# Dispenser.net
KiCad netlist of a schematic drawn in EAGLE
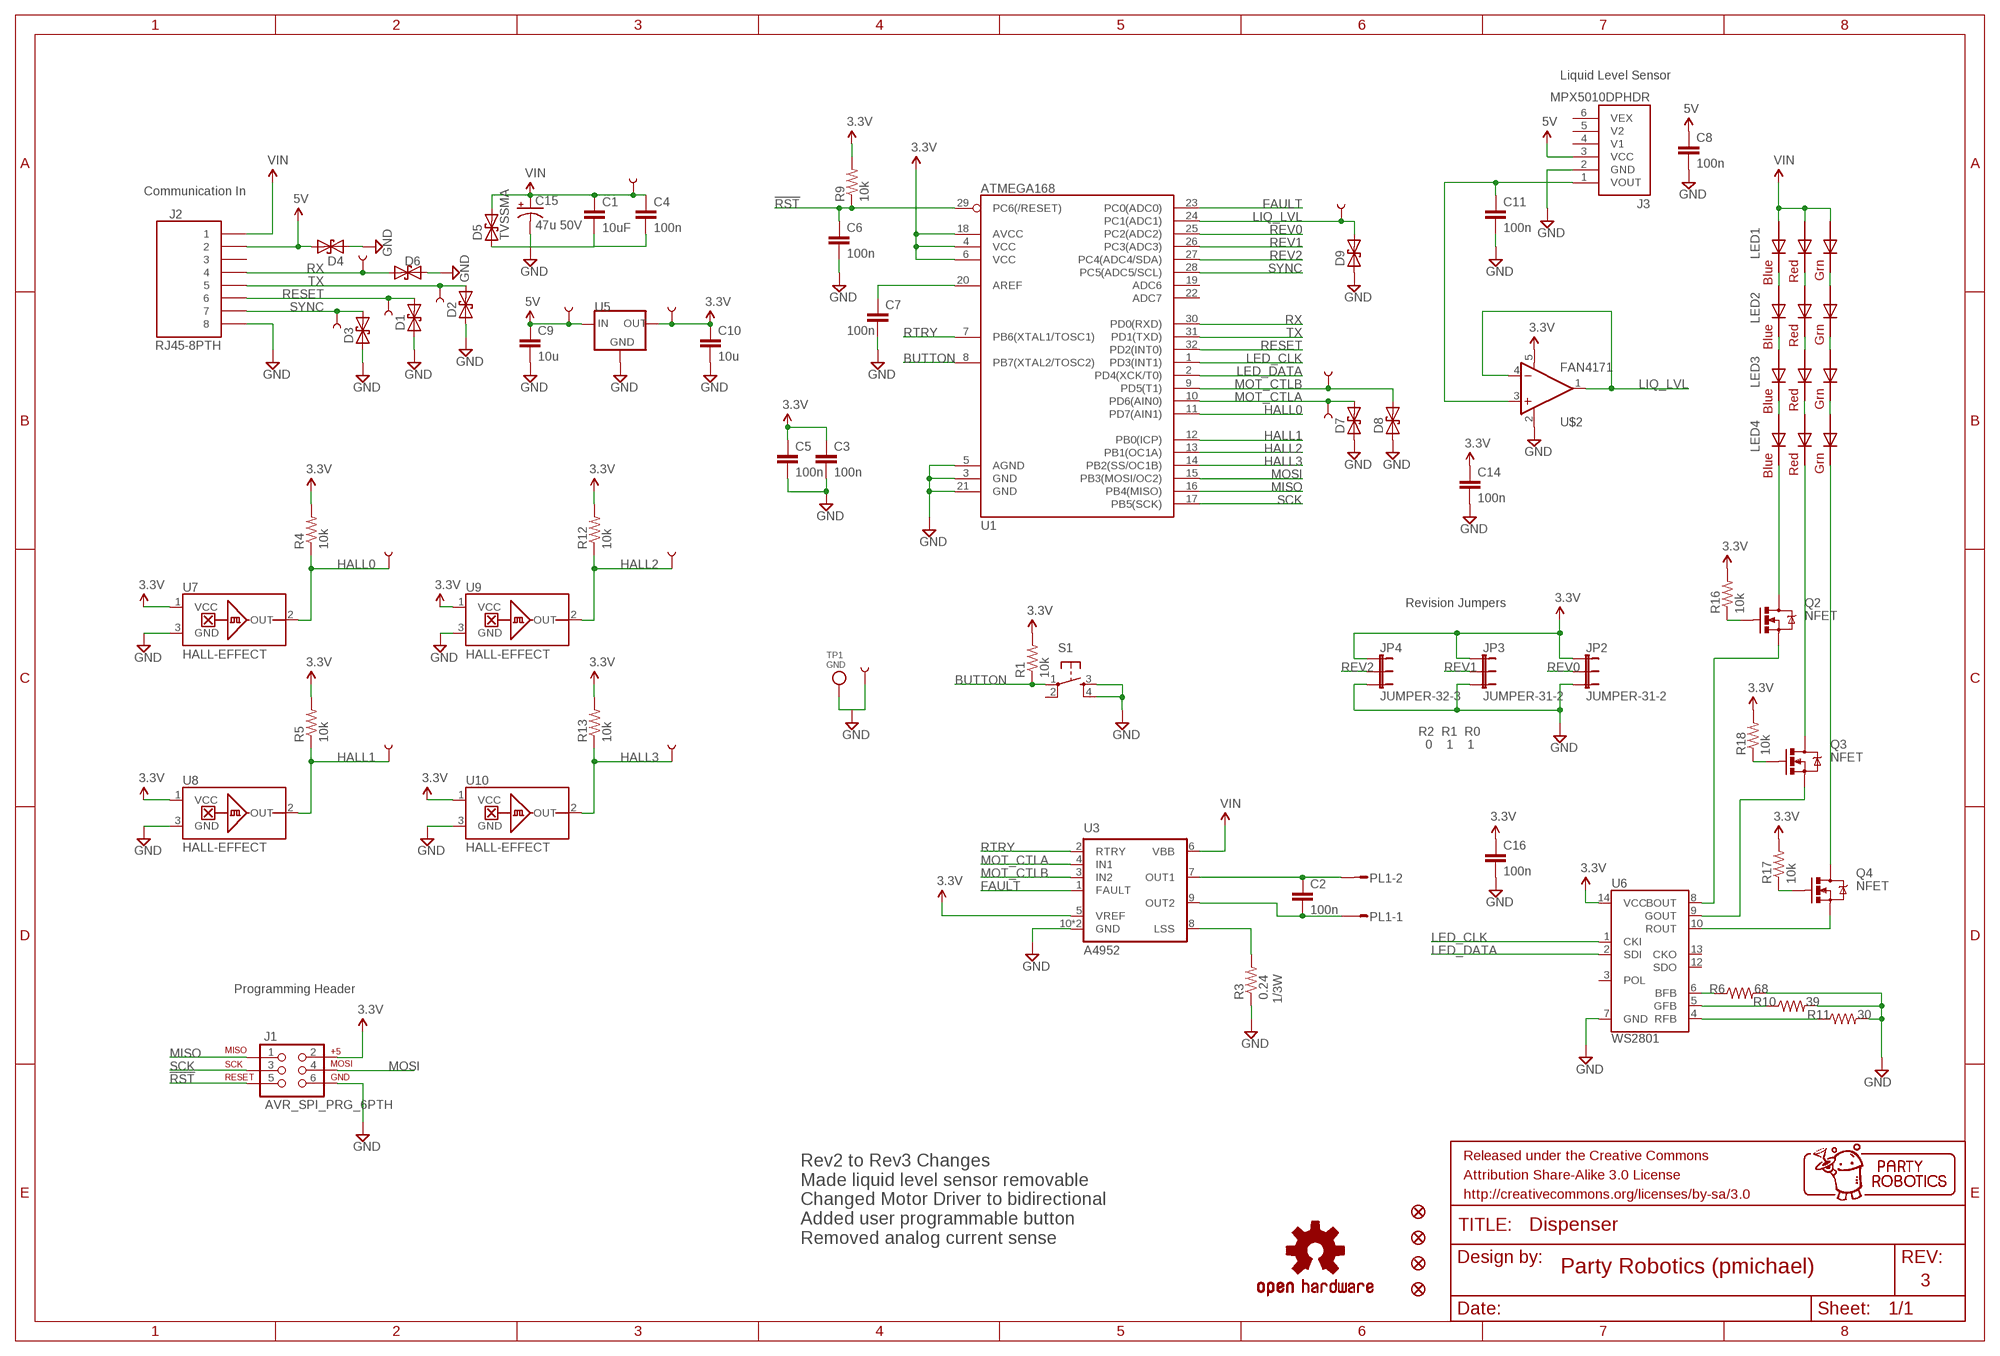
[diagram p0: schematic, sheet 1]

(export (version "E")
  (design (tool "Eeschema 10.0.6"))
  (components
    (comp (ref "C1")
      (value "10uF")
      (footprint "eagle-import:1206")
      (libsource (lib "eagle-import") (part "2.2UF-CERCAP-10009"))
    )
    (comp (ref "C2")
      (value "100n")
      (footprint "eagle-import:0603-CAP")
      (libsource (lib "eagle-import") (part "CAP0603-CAP"))
    )
    (comp (ref "C3")
      (value "100n")
      (footprint "eagle-import:0603-CAP")
      (libsource (lib "eagle-import") (part "CAP0603-CAP"))
    )
    (comp (ref "C4")
      (value "100n")
      (footprint "eagle-import:0603-CAP")
      (libsource (lib "eagle-import") (part "CAP0603-CAP"))
    )
    (comp (ref "C5")
      (value "100n")
      (footprint "eagle-import:0603-CAP")
      (libsource (lib "eagle-import") (part "CAP0603-CAP"))
    )
    (comp (ref "C6")
      (value "100n")
      (footprint "eagle-import:0603-CAP")
      (libsource (lib "eagle-import") (part "CAP0603-CAP"))
    )
    (comp (ref "C7")
      (value "100n")
      (footprint "eagle-import:0603-CAP")
      (libsource (lib "eagle-import") (part "CAP0603-CAP"))
    )
    (comp (ref "C8")
      (value "100n")
      (footprint "eagle-import:0603-CAP")
      (libsource (lib "eagle-import") (part "CAP0603-CAP"))
    )
    (comp (ref "C9")
      (value "10u")
      (footprint "eagle-import:0603-CAP")
      (libsource (lib "eagle-import") (part "SparkFun-Passives_CAP0603-CAP"))
    )
    (comp (ref "C10")
      (value "10u")
      (footprint "eagle-import:0603-CAP")
      (libsource (lib "eagle-import") (part "SparkFun-Passives_CAP0603-CAP"))
    )
    (comp (ref "C11")
      (value "100n")
      (footprint "eagle-import:0603-CAP")
      (libsource (lib "eagle-import") (part "CAP0603-CAP"))
    )
    (comp (ref "C14")
      (value "100n")
      (footprint "eagle-import:0603-CAP")
      (libsource (lib "eagle-import") (part "CAP0603-CAP"))
    )
    (comp (ref "C15")
      (value "47u 50V")
      (footprint "eagle-import:PANASONIC_D")
      (libsource (lib "eagle-import") (part "CAP_POLD"))
    )
    (comp (ref "C16")
      (value "100n")
      (footprint "eagle-import:0603-CAP")
      (libsource (lib "eagle-import") (part "CAP0603-CAP"))
    )
    (comp (ref "D1")
      (value "TVSSOD-923")
      (footprint "eagle-import:SOD-923")
      (libsource (lib "eagle-import") (part "TVSSOD-923"))
    )
    (comp (ref "D2")
      (value "TVSSOD-923")
      (footprint "eagle-import:SOD-923")
      (libsource (lib "eagle-import") (part "TVSSOD-923"))
    )
    (comp (ref "D3")
      (value "TVSSOD-923")
      (footprint "eagle-import:SOD-923")
      (libsource (lib "eagle-import") (part "TVSSOD-923"))
    )
    (comp (ref "D4")
      (value "TVSSOD-923")
      (footprint "eagle-import:SOD-923")
      (libsource (lib "eagle-import") (part "TVSSOD-923"))
    )
    (comp (ref "D5")
      (value "TVSSMA")
      (footprint "eagle-import:SMA-DIODE")
      (fields (field (name "MFG") "Bourns"))
      (libsource (lib "eagle-import") (part "TVSSMA"))
    )
    (comp (ref "D6")
      (value "TVSSOD-923")
      (footprint "eagle-import:SOD-923")
      (libsource (lib "eagle-import") (part "TVSSOD-923"))
    )
    (comp (ref "D7")
      (value "TVSSOD-923")
      (footprint "eagle-import:SOD-923")
      (libsource (lib "eagle-import") (part "TVSSOD-923"))
    )
    (comp (ref "D8")
      (value "TVSSOD-923")
      (footprint "eagle-import:SOD-923")
      (libsource (lib "eagle-import") (part "TVSSOD-923"))
    )
    (comp (ref "D9")
      (value "TVSSOD-923")
      (footprint "eagle-import:SOD-923")
      (libsource (lib "eagle-import") (part "TVSSOD-923"))
    )
    (comp (ref "FRAME3")
      (value "FRAME-LETTER")
      (footprint "eagle-import:CREATIVE_COMMONS")
      (libsource (lib "eagle-import") (part "FRAME-LETTER"))
    )
    (comp (ref "J1")
      (value "AVR_SPI_PRG_6PTH")
      (footprint "eagle-import:2X3")
      (libsource (lib "eagle-import") (part "AVR_SPI_PRG_6PTH"))
    )
    (comp (ref "J2")
      (value "RJ45-8PTH")
      (footprint "eagle-import:RJ45-8")
      (fields (field (name "MFG") "EDAC Inc"))
      (libsource (lib "eagle-import") (part "RJ45-8PTH"))
    )
    (comp (ref "J3")
      (value "MPX5010DPHDR")
      (footprint "eagle-import:MPX5010_HDR")
      (libsource (lib "eagle-import") (part "MPX5010DPHDR"))
    )
    (comp (ref "JP2")
      (value "JUMPER-31-2")
      (footprint "eagle-import:SJ_3_PASTE1&2")
      (libsource (lib "eagle-import") (part "JUMPER-31-2"))
    )
    (comp (ref "JP3")
      (value "JUMPER-31-2")
      (footprint "eagle-import:SJ_3_PASTE1&2")
      (libsource (lib "eagle-import") (part "JUMPER-31-2"))
    )
    (comp (ref "JP4")
      (value "JUMPER-32-3")
      (footprint "eagle-import:SJ_3_PASTE2&3")
      (libsource (lib "eagle-import") (part "JUMPER-32-3"))
    )
    (comp (ref "JP5")
      (value "FIDUCIAL1X2")
      (footprint "eagle-import:FIDUCIAL-1X2")
      (libsource (lib "eagle-import") (part "FIDUCIAL1X2"))
    )
    (comp (ref "JP6")
      (value "FIDUCIAL1X2")
      (footprint "eagle-import:FIDUCIAL-1X2")
      (libsource (lib "eagle-import") (part "FIDUCIAL1X2"))
    )
    (comp (ref "JP7")
      (value "FIDUCIAL1X2")
      (footprint "eagle-import:FIDUCIAL-1X2")
      (libsource (lib "eagle-import") (part "FIDUCIAL1X2"))
    )
    (comp (ref "JP8")
      (value "FIDUCIAL1X2")
      (footprint "eagle-import:FIDUCIAL-1X2")
      (libsource (lib "eagle-import") (part "FIDUCIAL1X2"))
    )
    (comp (ref "LED1")
      (value "RGBLED5050")
      (footprint "eagle-import:RGBLED5050")
      (libsource (lib "eagle-import") (part "RGBLED5050"))
    )
    (comp (ref "LED2")
      (value "RGBLED5050")
      (footprint "eagle-import:RGBLED5050")
      (libsource (lib "eagle-import") (part "RGBLED5050"))
    )
    (comp (ref "LED3")
      (value "RGBLED5050")
      (footprint "eagle-import:RGBLED5050")
      (libsource (lib "eagle-import") (part "RGBLED5050"))
    )
    (comp (ref "LED4")
      (value "RGBLED5050")
      (footprint "eagle-import:RGBLED5050")
      (libsource (lib "eagle-import") (part "RGBLED5050"))
    )
    (comp (ref "PL1")
      (value "DF3-02P")
      (footprint "eagle-import:DF3P-02")
      (libsource (lib "eagle-import") (part "DF3-02P"))
    )
    (comp (ref "Q2")
      (value "NFET")
      (footprint "eagle-import:SOT23-3")
      (libsource (lib "eagle-import") (part "MOSFET-NCHANNELSMD"))
    )
    (comp (ref "Q3")
      (value "NFET")
      (footprint "eagle-import:SOT23-3")
      (libsource (lib "eagle-import") (part "MOSFET-NCHANNELSMD"))
    )
    (comp (ref "Q4")
      (value "NFET")
      (footprint "eagle-import:SOT23-3")
      (libsource (lib "eagle-import") (part "MOSFET-NCHANNELSMD"))
    )
    (comp (ref "R1")
      (value "10k")
      (footprint "eagle-import:0603-RES")
      (libsource (lib "eagle-import") (part "RESISTOR0603-RES"))
    )
    (comp (ref "R3")
      (value "0.24")
      (footprint "eagle-import:0805")
      (libsource (lib "eagle-import") (part "RESISTOR0805-RES"))
    )
    (comp (ref "R4")
      (value "10k")
      (footprint "eagle-import:0603-RES")
      (libsource (lib "eagle-import") (part "RESISTOR0603-RES"))
    )
    (comp (ref "R5")
      (value "10k")
      (footprint "eagle-import:0603-RES")
      (libsource (lib "eagle-import") (part "RESISTOR0603-RES"))
    )
    (comp (ref "R6")
      (value "68")
      (footprint "eagle-import:0603-RES")
      (libsource (lib "eagle-import") (part "RESISTOR0603-RES"))
    )
    (comp (ref "R9")
      (value "10k")
      (footprint "eagle-import:0603-RES")
      (libsource (lib "eagle-import") (part "RESISTOR0603-RES"))
    )
    (comp (ref "R10")
      (value "39")
      (footprint "eagle-import:0603-RES")
      (libsource (lib "eagle-import") (part "RESISTOR0603-RES"))
    )
    (comp (ref "R11")
      (value "30")
      (footprint "eagle-import:0603-RES")
      (libsource (lib "eagle-import") (part "RESISTOR0603-RES"))
    )
    (comp (ref "R12")
      (value "10k")
      (footprint "eagle-import:0603-RES")
      (libsource (lib "eagle-import") (part "RESISTOR0603-RES"))
    )
    (comp (ref "R13")
      (value "10k")
      (footprint "eagle-import:0603-RES")
      (libsource (lib "eagle-import") (part "RESISTOR0603-RES"))
    )
    (comp (ref "R16")
      (value "10k")
      (footprint "eagle-import:0603-RES")
      (libsource (lib "eagle-import") (part "RESISTOR0603-RES"))
    )
    (comp (ref "R17")
      (value "10k")
      (footprint "eagle-import:0603-RES")
      (libsource (lib "eagle-import") (part "RESISTOR0603-RES"))
    )
    (comp (ref "R18")
      (value "10k")
      (footprint "eagle-import:0603-RES")
      (libsource (lib "eagle-import") (part "RESISTOR0603-RES"))
    )
    (comp (ref "S1")
      (value "TAC_SWITCHSMD")
      (footprint "eagle-import:TACTILE_SWITCH_SMD")
      (libsource (lib "eagle-import") (part "TAC_SWITCHSMD"))
    )
    (comp (ref "TP1")
      (value "GND")
      (footprint "eagle-import:TESTPOINT_SMT")
      (libsource (lib "eagle-import") (part "TESTPOINT"))
    )
    (comp (ref "TP2")
      (value "TEST-POINT0.08")
      (footprint "eagle-import:PAD_0.08")
      (libsource (lib "eagle-import") (part "TEST-POINT0.08"))
    )
    (comp (ref "TP3")
      (value "TEST-POINT0.08")
      (footprint "eagle-import:PAD_0.08")
      (libsource (lib "eagle-import") (part "TEST-POINT0.08"))
    )
    (comp (ref "TP4")
      (value "TEST-POINT0.08")
      (footprint "eagle-import:PAD_0.08")
      (libsource (lib "eagle-import") (part "TEST-POINT0.08"))
    )
    (comp (ref "TP5")
      (value "TEST-POINT0.08")
      (footprint "eagle-import:PAD_0.08")
      (libsource (lib "eagle-import") (part "TEST-POINT0.08"))
    )
    (comp (ref "TP6")
      (value "TEST-POINT0.08")
      (footprint "eagle-import:PAD_0.08")
      (libsource (lib "eagle-import") (part "TEST-POINT0.08"))
    )
    (comp (ref "TP7")
      (value "TEST-POINT3X5")
      (footprint "eagle-import:PAD.03X.05")
      (libsource (lib "eagle-import") (part "TEST-POINT3X5"))
    )
    (comp (ref "TP8")
      (value "TEST-POINT3X5")
      (footprint "eagle-import:PAD.03X.05")
      (libsource (lib "eagle-import") (part "TEST-POINT3X5"))
    )
    (comp (ref "TP9")
      (value "TEST-POINT3X5")
      (footprint "eagle-import:PAD.03X.05")
      (libsource (lib "eagle-import") (part "TEST-POINT3X5"))
    )
    (comp (ref "TP10")
      (value "TEST-POINT3X5")
      (footprint "eagle-import:PAD.03X.05")
      (libsource (lib "eagle-import") (part "TEST-POINT3X5"))
    )
    (comp (ref "TP11")
      (value "TEST-POINT3X5")
      (footprint "eagle-import:PAD.03X.05")
      (libsource (lib "eagle-import") (part "TEST-POINT3X5"))
    )
    (comp (ref "TP12")
      (value "TEST-POINT3X5")
      (footprint "eagle-import:PAD.03X.05")
      (libsource (lib "eagle-import") (part "TEST-POINT3X5"))
    )
    (comp (ref "TP13")
      (value "TEST-POINT0.08")
      (footprint "eagle-import:PAD_0.08")
      (libsource (lib "eagle-import") (part "TEST-POINT0.08"))
    )
    (comp (ref "TP14")
      (value "TEST-POINT0.08")
      (footprint "eagle-import:PAD_0.08")
      (libsource (lib "eagle-import") (part "TEST-POINT0.08"))
    )
    (comp (ref "TP15")
      (value "TEST-POINT0.08")
      (footprint "eagle-import:PAD_0.08")
      (libsource (lib "eagle-import") (part "TEST-POINT0.08"))
    )
    (comp (ref "TP16")
      (value "TEST-POINT0.08")
      (footprint "eagle-import:PAD_0.08")
      (libsource (lib "eagle-import") (part "TEST-POINT0.08"))
    )
    (comp (ref "U$1")
      (value "OSHW-LOGOM")
      (footprint "eagle-import:OSHW-LOGO-M")
      (libsource (lib "eagle-import") (part "OSHW-LOGOM"))
    )
    (comp (ref "U$2")
      (value "FAN4171")
      (footprint "eagle-import:SOT23-5")
      (libsource (lib "eagle-import") (part "OPA344"))
    )
    (comp (ref "U1")
      (value "ATMEGA168")
      (footprint "eagle-import:TQFP32-08")
      (libsource (lib "eagle-import") (part "ATMEGA168"))
    )
    (comp (ref "U3")
      (value "A4952")
      (footprint "eagle-import:MSOP-10-GNDPAD")
      (libsource (lib "eagle-import") (part "A4952"))
    )
    (comp (ref "U5")
      (value "VREG-5V-LDO-AP1117SOT89-3L")
      (footprint "eagle-import:SOT89-3L")
      (libsource (lib "eagle-import") (part "VREG-5V-LDO-AP1117SOT89-3L"))
    )
    (comp (ref "U6")
      (value "WS2801")
      (footprint "eagle-import:SOP-14")
      (libsource (lib "eagle-import") (part "WS2801"))
    )
    (comp (ref "U7")
      (value "HALL-EFFECT")
      (footprint "eagle-import:SOT23-3")
      (libsource (lib "eagle-import") (part "HALL-EFFECT"))
    )
    (comp (ref "U8")
      (value "HALL-EFFECT")
      (footprint "eagle-import:SOT23-3")
      (libsource (lib "eagle-import") (part "HALL-EFFECT"))
    )
    (comp (ref "U9")
      (value "HALL-EFFECT")
      (footprint "eagle-import:SOT23-3")
      (libsource (lib "eagle-import") (part "HALL-EFFECT"))
    )
    (comp (ref "U10")
      (value "HALL-EFFECT")
      (footprint "eagle-import:SOT23-3")
      (libsource (lib "eagle-import") (part "HALL-EFFECT"))
    )
  )
  (nets
    (net (code "1") (name "/1{slash}3W") (class "Default")
      (node (ref "R3") (pin "2") (pinfunction "2_2") (pintype "passive"))
      (node (ref "U3") (pin "8") (pinfunction "LSS_8") (pintype "power_in"))
    )
    (net (code "2") (name "/BUTTON") (class "Default")
      (node (ref "R1") (pin "1") (pinfunction "1_1") (pintype "passive"))
      (node (ref "S1") (pin "1") (pinfunction "1_1") (pintype "passive"))
      (node (ref "U1") (pin "8") (pinfunction "PB7(XTAL2/TOSC2)_8") (pintype "bidirectional"))
    )
    (net (code "3") (name "/FAULT") (class "Default")
      (node (ref "U1") (pin "23") (pinfunction "PC0(ADC0)_23") (pintype "bidirectional"))
      (node (ref "U3") (pin "1") (pinfunction "FAULT_1") (pintype "output"))
    )
    (net (code "4") (name "/HALL0") (class "Default")
      (node (ref "R4") (pin "1") (pinfunction "1_1") (pintype "passive"))
      (node (ref "TP10") (pin "P$1") (pinfunction "1_P$1") (pintype "bidirectional"))
      (node (ref "U1") (pin "11") (pinfunction "PD7(AIN1)_11") (pintype "bidirectional"))
      (node (ref "U7") (pin "2") (pinfunction "OUT_2") (pintype "bidirectional"))
    )
    (net (code "5") (name "/HALL1") (class "Default")
      (node (ref "R5") (pin "1") (pinfunction "1_1") (pintype "passive"))
      (node (ref "TP11") (pin "P$1") (pinfunction "1_P$1") (pintype "bidirectional"))
      (node (ref "U1") (pin "12") (pinfunction "PB0(ICP)_12") (pintype "bidirectional"))
      (node (ref "U8") (pin "2") (pinfunction "OUT_2") (pintype "bidirectional"))
    )
    (net (code "6") (name "/HALL2") (class "Default")
      (node (ref "R12") (pin "1") (pinfunction "1_1") (pintype "passive"))
      (node (ref "TP9") (pin "P$1") (pinfunction "1_P$1") (pintype "bidirectional"))
      (node (ref "U1") (pin "13") (pinfunction "PB1(OC1A)_13") (pintype "bidirectional"))
      (node (ref "U9") (pin "2") (pinfunction "OUT_2") (pintype "bidirectional"))
    )
    (net (code "7") (name "/HALL3") (class "Default")
      (node (ref "R13") (pin "1") (pinfunction "1_1") (pintype "passive"))
      (node (ref "TP12") (pin "P$1") (pinfunction "1_P$1") (pintype "bidirectional"))
      (node (ref "U1") (pin "14") (pinfunction "PB2(SS/OC1B)_14") (pintype "bidirectional"))
      (node (ref "U10") (pin "2") (pinfunction "OUT_2") (pintype "bidirectional"))
    )
    (net (code "8") (name "/LED_CLK") (class "Default")
      (node (ref "U1") (pin "1") (pinfunction "PD3(INT1)_1") (pintype "bidirectional"))
      (node (ref "U6") (pin "1") (pinfunction "CKI_1") (pintype "bidirectional"))
    )
    (net (code "9") (name "/LED_DATA") (class "Default")
      (node (ref "U1") (pin "2") (pinfunction "PD4(XCK/T0)_2") (pintype "bidirectional"))
      (node (ref "U6") (pin "2") (pinfunction "SDI_2") (pintype "bidirectional"))
    )
    (net (code "10") (name "/LIQ_LVL") (class "Default")
      (node (ref "D9") (pin "C") (pinfunction "2_C") (pintype "passive"))
      (node (ref "TP14") (pin "P$1") (pinfunction "1_P$1") (pintype "bidirectional"))
      (node (ref "U$2") (pin "1") (pinfunction "OUT_1") (pintype "output"))
      (node (ref "U$2") (pin "4") (pinfunction "-IN_4") (pintype "input"))
      (node (ref "U1") (pin "24") (pinfunction "PC1(ADC1)_24") (pintype "bidirectional"))
    )
    (net (code "11") (name "/MISO") (class "Default")
      (node (ref "J1") (pin "1") (pinfunction "1_1") (pintype "passive"))
      (node (ref "U1") (pin "16") (pinfunction "PB4(MISO)_16") (pintype "bidirectional"))
    )
    (net (code "12") (name "/MOSI") (class "Default")
      (node (ref "J1") (pin "4") (pinfunction "4_4") (pintype "passive"))
      (node (ref "U1") (pin "15") (pinfunction "PB3(MOSI/OC2)_15") (pintype "bidirectional"))
    )
    (net (code "13") (name "/MOT_CTLA") (class "Default")
      (node (ref "D7") (pin "C") (pinfunction "2_C") (pintype "passive"))
      (node (ref "TP8") (pin "P$1") (pinfunction "1_P$1") (pintype "bidirectional"))
      (node (ref "U1") (pin "10") (pinfunction "PD6(AIN0)_10") (pintype "bidirectional"))
      (node (ref "U3") (pin "4") (pinfunction "IN1_4") (pintype "input"))
    )
    (net (code "14") (name "/MOT_CTLB") (class "Default")
      (node (ref "D8") (pin "C") (pinfunction "2_C") (pintype "passive"))
      (node (ref "TP7") (pin "P$1") (pinfunction "1_P$1") (pintype "bidirectional"))
      (node (ref "U1") (pin "9") (pinfunction "PD5(T1)_9") (pintype "bidirectional"))
      (node (ref "U3") (pin "3") (pinfunction "IN2_3") (pintype "input"))
    )
    (net (code "15") (name "/RESET") (class "Default")
      (node (ref "D1") (pin "C") (pinfunction "2_C") (pintype "passive"))
      (node (ref "J2") (pin "6") (pinfunction "6_6") (pintype "bidirectional"))
      (node (ref "TP13") (pin "P$1") (pinfunction "1_P$1") (pintype "bidirectional"))
      (node (ref "U1") (pin "32") (pinfunction "PD2(INT0)_32") (pintype "bidirectional"))
    )
    (net (code "16") (name "/REV0") (class "Default")
      (node (ref "JP2") (pin "2") (pinfunction "2_2") (pintype "passive"))
      (node (ref "U1") (pin "25") (pinfunction "PC2(ADC2)_25") (pintype "bidirectional"))
    )
    (net (code "17") (name "/REV1") (class "Default")
      (node (ref "JP3") (pin "2") (pinfunction "2_2") (pintype "passive"))
      (node (ref "U1") (pin "26") (pinfunction "PC3(ADC3)_26") (pintype "bidirectional"))
    )
    (net (code "18") (name "/REV2") (class "Default")
      (node (ref "JP4") (pin "2") (pinfunction "2_2") (pintype "passive"))
      (node (ref "U1") (pin "27") (pinfunction "PC4(ADC4/SDA)_27") (pintype "bidirectional"))
    )
    (net (code "19") (name "/RTRY") (class "Default")
      (node (ref "U1") (pin "7") (pinfunction "PB6(XTAL1/TOSC1)_7") (pintype "bidirectional"))
      (node (ref "U3") (pin "2") (pinfunction "RTRY_2") (pintype "input"))
    )
    (net (code "20") (name "/RX") (class "Default")
      (node (ref "D6") (pin "C") (pinfunction "2_C") (pintype "passive"))
      (node (ref "J2") (pin "4") (pinfunction "4_4") (pintype "bidirectional"))
      (node (ref "TP4") (pin "P$1") (pinfunction "1_P$1") (pintype "bidirectional"))
      (node (ref "U1") (pin "30") (pinfunction "PD0(RXD)_30") (pintype "bidirectional"))
    )
    (net (code "21") (name "/SCK") (class "Default")
      (node (ref "J1") (pin "3") (pinfunction "3_3") (pintype "passive"))
      (node (ref "U1") (pin "17") (pinfunction "PB5(SCK)_17") (pintype "bidirectional"))
    )
    (net (code "22") (name "/SYNC") (class "Default")
      (node (ref "D3") (pin "C") (pinfunction "2_C") (pintype "passive"))
      (node (ref "J2") (pin "7") (pinfunction "7_7") (pintype "bidirectional"))
      (node (ref "TP15") (pin "P$1") (pinfunction "1_P$1") (pintype "bidirectional"))
      (node (ref "U1") (pin "28") (pinfunction "PC5(ADC5/SCL)_28") (pintype "bidirectional"))
    )
    (net (code "23") (name "/TX") (class "Default")
      (node (ref "D2") (pin "C") (pinfunction "2_C") (pintype "passive"))
      (node (ref "J2") (pin "5") (pinfunction "5_5") (pintype "bidirectional"))
      (node (ref "TP5") (pin "P$1") (pinfunction "1_P$1") (pintype "bidirectional"))
      (node (ref "U1") (pin "31") (pinfunction "PD1(TXD)_31") (pintype "bidirectional"))
    )
    (net (code "24") (name "/~{RST}") (class "Default")
      (node (ref "C6") (pin "1") (pinfunction "1_1") (pintype "passive"))
      (node (ref "J1") (pin "5") (pinfunction "5_5") (pintype "passive"))
      (node (ref "R9") (pin "1") (pinfunction "1_1") (pintype "passive"))
      (node (ref "U1") (pin "29") (pinfunction "PC6(/RESET)_29") (pintype "bidirectional"))
    )
    (net (code "25") (name "3.3V") (class "Default")
      (node (ref "C10") (pin "1") (pinfunction "1_1") (pintype "passive"))
      (node (ref "C14") (pin "1") (pinfunction "1_1") (pintype "passive"))
      (node (ref "C16") (pin "1") (pinfunction "1_1") (pintype "passive"))
      (node (ref "C3") (pin "1") (pinfunction "1_1") (pintype "passive"))
      (node (ref "C5") (pin "1") (pinfunction "1_1") (pintype "passive"))
      (node (ref "J1") (pin "2") (pinfunction "2_2") (pintype "passive"))
      (node (ref "JP2") (pin "1") (pinfunction "1_1") (pintype "passive"))
      (node (ref "JP3") (pin "1") (pinfunction "1_1") (pintype "passive"))
      (node (ref "JP4") (pin "1") (pinfunction "1_1") (pintype "passive"))
      (node (ref "R1") (pin "2") (pinfunction "2_2") (pintype "passive"))
      (node (ref "R12") (pin "2") (pinfunction "2_2") (pintype "passive"))
      (node (ref "R13") (pin "2") (pinfunction "2_2") (pintype "passive"))
      (node (ref "R16") (pin "2") (pinfunction "2_2") (pintype "passive"))
      (node (ref "R17") (pin "2") (pinfunction "2_2") (pintype "passive"))
      (node (ref "R18") (pin "2") (pinfunction "2_2") (pintype "passive"))
      (node (ref "R4") (pin "2") (pinfunction "2_2") (pintype "passive"))
      (node (ref "R5") (pin "2") (pinfunction "2_2") (pintype "passive"))
      (node (ref "R9") (pin "2") (pinfunction "2_2") (pintype "passive"))
      (node (ref "TP16") (pin "P$1") (pinfunction "1_P$1") (pintype "bidirectional"))
      (node (ref "U$2") (pin "5") (pinfunction "V+_5") (pintype "power_in"))
      (node (ref "U1") (pin "18") (pinfunction "AVCC_18") (pintype "bidirectional"))
      (node (ref "U1") (pin "4") (pinfunction "VCC_4") (pintype "bidirectional"))
      (node (ref "U1") (pin "6") (pinfunction "VCC_6") (pintype "bidirectional"))
      (node (ref "U10") (pin "1") (pinfunction "VCC_1") (pintype "bidirectional"))
      (node (ref "U3") (pin "5") (pinfunction "VREF_5") (pintype "passive"))
      (node (ref "U5") (pin "2") (pinfunction "OUT_2") (pintype "output"))
      (node (ref "U5") (pin "2.1") (pinfunction "OUT_2.1") (pintype "output"))
      (node (ref "U6") (pin "14") (pinfunction "VCC_14") (pintype "bidirectional"))
      (node (ref "U7") (pin "1") (pinfunction "VCC_1") (pintype "bidirectional"))
      (node (ref "U8") (pin "1") (pinfunction "VCC_1") (pintype "bidirectional"))
      (node (ref "U9") (pin "1") (pinfunction "VCC_1") (pintype "bidirectional"))
    )
    (net (code "26") (name "5V") (class "Default")
      (node (ref "C8") (pin "1") (pinfunction "1_1") (pintype "passive"))
      (node (ref "C9") (pin "1") (pinfunction "1_1") (pintype "passive"))
      (node (ref "D4") (pin "C") (pinfunction "2_C") (pintype "passive"))
      (node (ref "J2") (pin "2") (pinfunction "2_2") (pintype "bidirectional"))
      (node (ref "J3") (pin "3") (pinfunction "VCC_3") (pintype "bidirectional"))
      (node (ref "TP3") (pin "P$1") (pinfunction "1_P$1") (pintype "bidirectional"))
      (node (ref "U5") (pin "3") (pinfunction "IN_3") (pintype "input"))
    )
    (net (code "27") (name "GND") (class "Default")
      (node (ref "C1") (pin "2") (pinfunction "2_2") (pintype "passive"))
      (node (ref "C10") (pin "2") (pinfunction "2_2") (pintype "passive"))
      (node (ref "C11") (pin "2") (pinfunction "2_2") (pintype "passive"))
      (node (ref "C14") (pin "2") (pinfunction "2_2") (pintype "passive"))
      (node (ref "C15") (pin "-") (pinfunction "-_-") (pintype "passive"))
      (node (ref "C16") (pin "2") (pinfunction "2_2") (pintype "passive"))
      (node (ref "C3") (pin "2") (pinfunction "2_2") (pintype "passive"))
      (node (ref "C4") (pin "2") (pinfunction "2_2") (pintype "passive"))
      (node (ref "C5") (pin "2") (pinfunction "2_2") (pintype "passive"))
      (node (ref "C6") (pin "2") (pinfunction "2_2") (pintype "passive"))
      (node (ref "C7") (pin "2") (pinfunction "2_2") (pintype "passive"))
      (node (ref "C8") (pin "2") (pinfunction "2_2") (pintype "passive"))
      (node (ref "C9") (pin "2") (pinfunction "2_2") (pintype "passive"))
      (node (ref "D1") (pin "A") (pinfunction "1_A") (pintype "passive"))
      (node (ref "D2") (pin "A") (pinfunction "1_A") (pintype "passive"))
      (node (ref "D3") (pin "A") (pinfunction "1_A") (pintype "passive"))
      (node (ref "D4") (pin "A") (pinfunction "1_A") (pintype "passive"))
      (node (ref "D5") (pin "A") (pinfunction "1_A") (pintype "passive"))
      (node (ref "D6") (pin "A") (pinfunction "1_A") (pintype "passive"))
      (node (ref "D7") (pin "A") (pinfunction "1_A") (pintype "passive"))
      (node (ref "D8") (pin "A") (pinfunction "1_A") (pintype "passive"))
      (node (ref "D9") (pin "A") (pinfunction "1_A") (pintype "passive"))
      (node (ref "J1") (pin "6") (pinfunction "6_6") (pintype "passive"))
      (node (ref "J2") (pin "8") (pinfunction "8_8") (pintype "bidirectional"))
      (node (ref "J3") (pin "2") (pinfunction "GND_2") (pintype "bidirectional"))
      (node (ref "JP2") (pin "3") (pinfunction "3_3") (pintype "passive"))
      (node (ref "JP3") (pin "3") (pinfunction "3_3") (pintype "passive"))
      (node (ref "JP4") (pin "3") (pinfunction "3_3") (pintype "passive"))
      (node (ref "R10") (pin "2") (pinfunction "2_2") (pintype "passive"))
      (node (ref "R11") (pin "2") (pinfunction "2_2") (pintype "passive"))
      (node (ref "R3") (pin "1") (pinfunction "1_1") (pintype "passive"))
      (node (ref "R6") (pin "2") (pinfunction "2_2") (pintype "passive"))
      (node (ref "S1") (pin "3") (pinfunction "3_3") (pintype "passive"))
      (node (ref "S1") (pin "4") (pinfunction "4_4") (pintype "passive"))
      (node (ref "TP1") (pin "P$1") (pinfunction "P$1_P$1") (pintype "bidirectional"))
      (node (ref "TP2") (pin "P$1") (pinfunction "1_P$1") (pintype "bidirectional"))
      (node (ref "U$2") (pin "2") (pinfunction "V-_2") (pintype "power_in"))
      (node (ref "U1") (pin "21") (pinfunction "GND_21") (pintype "bidirectional"))
      (node (ref "U1") (pin "3") (pinfunction "GND_3") (pintype "bidirectional"))
      (node (ref "U1") (pin "5") (pinfunction "AGND_5") (pintype "bidirectional"))
      (node (ref "U10") (pin "3") (pinfunction "GND_3") (pintype "bidirectional"))
      (node (ref "U3") (pin "10") (pinfunction "GND_10") (pintype "power_in"))
      (node (ref "U3") (pin "GND") (pinfunction "GND_GND") (pintype "power_in"))
      (node (ref "U5") (pin "1") (pinfunction "GND_1") (pintype "input"))
      (node (ref "U6") (pin "7") (pinfunction "GND_7") (pintype "bidirectional"))
      (node (ref "U7") (pin "3") (pinfunction "GND_3") (pintype "bidirectional"))
      (node (ref "U8") (pin "3") (pinfunction "GND_3") (pintype "bidirectional"))
      (node (ref "U9") (pin "3") (pinfunction "GND_3") (pintype "bidirectional"))
    )
    (net (code "28") (name "Net-(J3-VOUT)") (class "Default")
      (node (ref "C11") (pin "1") (pinfunction "1_1") (pintype "passive"))
      (node (ref "J3") (pin "1") (pinfunction "VOUT_1") (pintype "bidirectional"))
      (node (ref "U$2") (pin "3") (pinfunction "+IN_3") (pintype "input"))
    )
    (net (code "29") (name "Net-(LED1-BLUE_C)") (class "Default")
      (node (ref "LED1") (pin "6") (pinfunction "BLUE_C_6") (pintype "bidirectional"))
      (node (ref "LED2") (pin "1") (pinfunction "BLUE_A_1") (pintype "bidirectional"))
    )
    (net (code "30") (name "Net-(LED1-GREEN_C)") (class "Default")
      (node (ref "LED1") (pin "4") (pinfunction "GREEN_C_4") (pintype "bidirectional"))
      (node (ref "LED2") (pin "3") (pinfunction "GREEN_A_3") (pintype "bidirectional"))
    )
    (net (code "31") (name "Net-(LED1-RED_C)") (class "Default")
      (node (ref "LED1") (pin "5") (pinfunction "RED_C_5") (pintype "bidirectional"))
      (node (ref "LED2") (pin "2") (pinfunction "RED_A_2") (pintype "bidirectional"))
    )
    (net (code "32") (name "Net-(LED2-BLUE_C)") (class "Default")
      (node (ref "LED2") (pin "6") (pinfunction "BLUE_C_6") (pintype "bidirectional"))
      (node (ref "LED3") (pin "1") (pinfunction "BLUE_A_1") (pintype "bidirectional"))
    )
    (net (code "33") (name "Net-(LED2-GREEN_C)") (class "Default")
      (node (ref "LED2") (pin "4") (pinfunction "GREEN_C_4") (pintype "bidirectional"))
      (node (ref "LED3") (pin "3") (pinfunction "GREEN_A_3") (pintype "bidirectional"))
    )
    (net (code "34") (name "Net-(LED2-RED_C)") (class "Default")
      (node (ref "LED2") (pin "5") (pinfunction "RED_C_5") (pintype "bidirectional"))
      (node (ref "LED3") (pin "2") (pinfunction "RED_A_2") (pintype "bidirectional"))
    )
    (net (code "35") (name "Net-(LED3-BLUE_C)") (class "Default")
      (node (ref "LED3") (pin "6") (pinfunction "BLUE_C_6") (pintype "bidirectional"))
      (node (ref "LED4") (pin "1") (pinfunction "BLUE_A_1") (pintype "bidirectional"))
    )
    (net (code "36") (name "Net-(LED3-GREEN_C)") (class "Default")
      (node (ref "LED3") (pin "4") (pinfunction "GREEN_C_4") (pintype "bidirectional"))
      (node (ref "LED4") (pin "3") (pinfunction "GREEN_A_3") (pintype "bidirectional"))
    )
    (net (code "37") (name "Net-(LED3-RED_C)") (class "Default")
      (node (ref "LED3") (pin "5") (pinfunction "RED_C_5") (pintype "bidirectional"))
      (node (ref "LED4") (pin "2") (pinfunction "RED_A_2") (pintype "bidirectional"))
    )
    (net (code "38") (name "Net-(LED4-BLUE_C)") (class "Default")
      (node (ref "LED4") (pin "6") (pinfunction "BLUE_C_6") (pintype "bidirectional"))
      (node (ref "Q2") (pin "3") (pinfunction "D_3") (pintype "passive"))
    )
    (net (code "39") (name "Net-(LED4-GREEN_C)") (class "Default")
      (node (ref "LED4") (pin "4") (pinfunction "GREEN_C_4") (pintype "bidirectional"))
      (node (ref "Q4") (pin "3") (pinfunction "D_3") (pintype "passive"))
    )
    (net (code "40") (name "Net-(LED4-RED_C)") (class "Default")
      (node (ref "LED4") (pin "5") (pinfunction "RED_C_5") (pintype "bidirectional"))
      (node (ref "Q3") (pin "3") (pinfunction "D_3") (pintype "passive"))
    )
    (net (code "41") (name "Net-(PL1A-S)") (class "Default")
      (node (ref "C2") (pin "2") (pinfunction "2_2") (pintype "passive"))
      (node (ref "PL1") (pin "1") (pinfunction "S_1") (pintype "passive"))
      (node (ref "U3") (pin "9") (pinfunction "OUT2_9") (pintype "output"))
    )
    (net (code "42") (name "Net-(PL1B-S)") (class "Default")
      (node (ref "C2") (pin "1") (pinfunction "1_1") (pintype "passive"))
      (node (ref "PL1") (pin "2") (pinfunction "S_2") (pintype "passive"))
      (node (ref "U3") (pin "7") (pinfunction "OUT1_7") (pintype "output"))
    )
    (net (code "43") (name "Net-(Q2-G)") (class "Default")
      (node (ref "Q2") (pin "1") (pinfunction "G_1") (pintype "passive"))
      (node (ref "R16") (pin "1") (pinfunction "1_1") (pintype "passive"))
    )
    (net (code "44") (name "Net-(Q2-S)") (class "Default")
      (node (ref "Q2") (pin "2") (pinfunction "S_2") (pintype "passive"))
      (node (ref "U6") (pin "8") (pinfunction "BOUT_8") (pintype "bidirectional"))
    )
    (net (code "45") (name "Net-(Q3-G)") (class "Default")
      (node (ref "Q3") (pin "1") (pinfunction "G_1") (pintype "passive"))
      (node (ref "R18") (pin "1") (pinfunction "1_1") (pintype "passive"))
    )
    (net (code "46") (name "Net-(Q3-S)") (class "Default")
      (node (ref "Q3") (pin "2") (pinfunction "S_2") (pintype "passive"))
      (node (ref "U6") (pin "9") (pinfunction "GOUT_9") (pintype "bidirectional"))
    )
    (net (code "47") (name "Net-(Q4-G)") (class "Default")
      (node (ref "Q4") (pin "1") (pinfunction "G_1") (pintype "passive"))
      (node (ref "R17") (pin "1") (pinfunction "1_1") (pintype "passive"))
    )
    (net (code "48") (name "Net-(Q4-S)") (class "Default")
      (node (ref "Q4") (pin "2") (pinfunction "S_2") (pintype "passive"))
      (node (ref "U6") (pin "10") (pinfunction "ROUT_10") (pintype "bidirectional"))
    )
    (net (code "49") (name "Net-(U1-AREF)") (class "Default")
      (node (ref "C7") (pin "1") (pinfunction "1_1") (pintype "passive"))
      (node (ref "U1") (pin "20") (pinfunction "AREF_20") (pintype "bidirectional"))
    )
    (net (code "50") (name "Net-(U6-BFB)") (class "Default")
      (node (ref "R6") (pin "1") (pinfunction "1_1") (pintype "passive"))
      (node (ref "U6") (pin "6") (pinfunction "BFB_6") (pintype "bidirectional"))
    )
    (net (code "51") (name "Net-(U6-GFB)") (class "Default")
      (node (ref "R10") (pin "1") (pinfunction "1_1") (pintype "passive"))
      (node (ref "U6") (pin "5") (pinfunction "GFB_5") (pintype "bidirectional"))
    )
    (net (code "52") (name "Net-(U6-RFB)") (class "Default")
      (node (ref "R11") (pin "1") (pinfunction "1_1") (pintype "passive"))
      (node (ref "U6") (pin "4") (pinfunction "RFB_4") (pintype "bidirectional"))
    )
    (net (code "53") (name "VIN") (class "Default")
      (node (ref "C1") (pin "1") (pinfunction "1_1") (pintype "passive"))
      (node (ref "C15") (pin "+") (pinfunction "+_+") (pintype "passive"))
      (node (ref "C4") (pin "1") (pinfunction "1_1") (pintype "passive"))
      (node (ref "D5") (pin "C") (pinfunction "2_C") (pintype "passive"))
      (node (ref "J2") (pin "1") (pinfunction "1_1") (pintype "bidirectional"))
      (node (ref "LED1") (pin "1") (pinfunction "BLUE_A_1") (pintype "bidirectional"))
      (node (ref "LED1") (pin "2") (pinfunction "RED_A_2") (pintype "bidirectional"))
      (node (ref "LED1") (pin "3") (pinfunction "GREEN_A_3") (pintype "bidirectional"))
      (node (ref "TP6") (pin "P$1") (pinfunction "1_P$1") (pintype "bidirectional"))
      (node (ref "U3") (pin "6") (pinfunction "VBB_6") (pintype "input"))
    )
    (net (code "54") (name "unconnected-(J2-Pad3)") (class "Default")
      (node (ref "J2") (pin "3") (pinfunction "3_3") (pintype "bidirectional"))
    )
    (net (code "55") (name "unconnected-(J3-V1-Pad4)") (class "Default")
      (node (ref "J3") (pin "4") (pinfunction "V1_4") (pintype "bidirectional"))
    )
    (net (code "56") (name "unconnected-(J3-V2-Pad5)") (class "Default")
      (node (ref "J3") (pin "5") (pinfunction "V2_5") (pintype "bidirectional"))
    )
    (net (code "57") (name "unconnected-(J3-VEX-Pad6)") (class "Default")
      (node (ref "J3") (pin "6") (pinfunction "VEX_6") (pintype "bidirectional"))
    )
    (net (code "58") (name "unconnected-(S1-Pad2)") (class "Default")
      (node (ref "S1") (pin "2") (pinfunction "2_2") (pintype "passive"))
    )
    (net (code "59") (name "unconnected-(U1-ADC6-Pad19)") (class "Default")
      (node (ref "U1") (pin "19") (pinfunction "ADC6_19") (pintype "bidirectional"))
    )
    (net (code "60") (name "unconnected-(U1-ADC7-Pad22)") (class "Default")
      (node (ref "U1") (pin "22") (pinfunction "ADC7_22") (pintype "bidirectional"))
    )
    (net (code "61") (name "unconnected-(U6-CKO-Pad13)") (class "Default")
      (node (ref "U6") (pin "13") (pinfunction "CKO_13") (pintype "bidirectional"))
    )
    (net (code "62") (name "unconnected-(U6-POL-Pad3)") (class "Default")
      (node (ref "U6") (pin "3") (pinfunction "POL_3") (pintype "bidirectional"))
    )
    (net (code "63") (name "unconnected-(U6-SDO-Pad12)") (class "Default")
      (node (ref "U6") (pin "12") (pinfunction "SDO_12") (pintype "bidirectional"))
    )
  )
)
